# amiketo_2hm.net
KiCad netlist of a schematic drawn in EAGLE
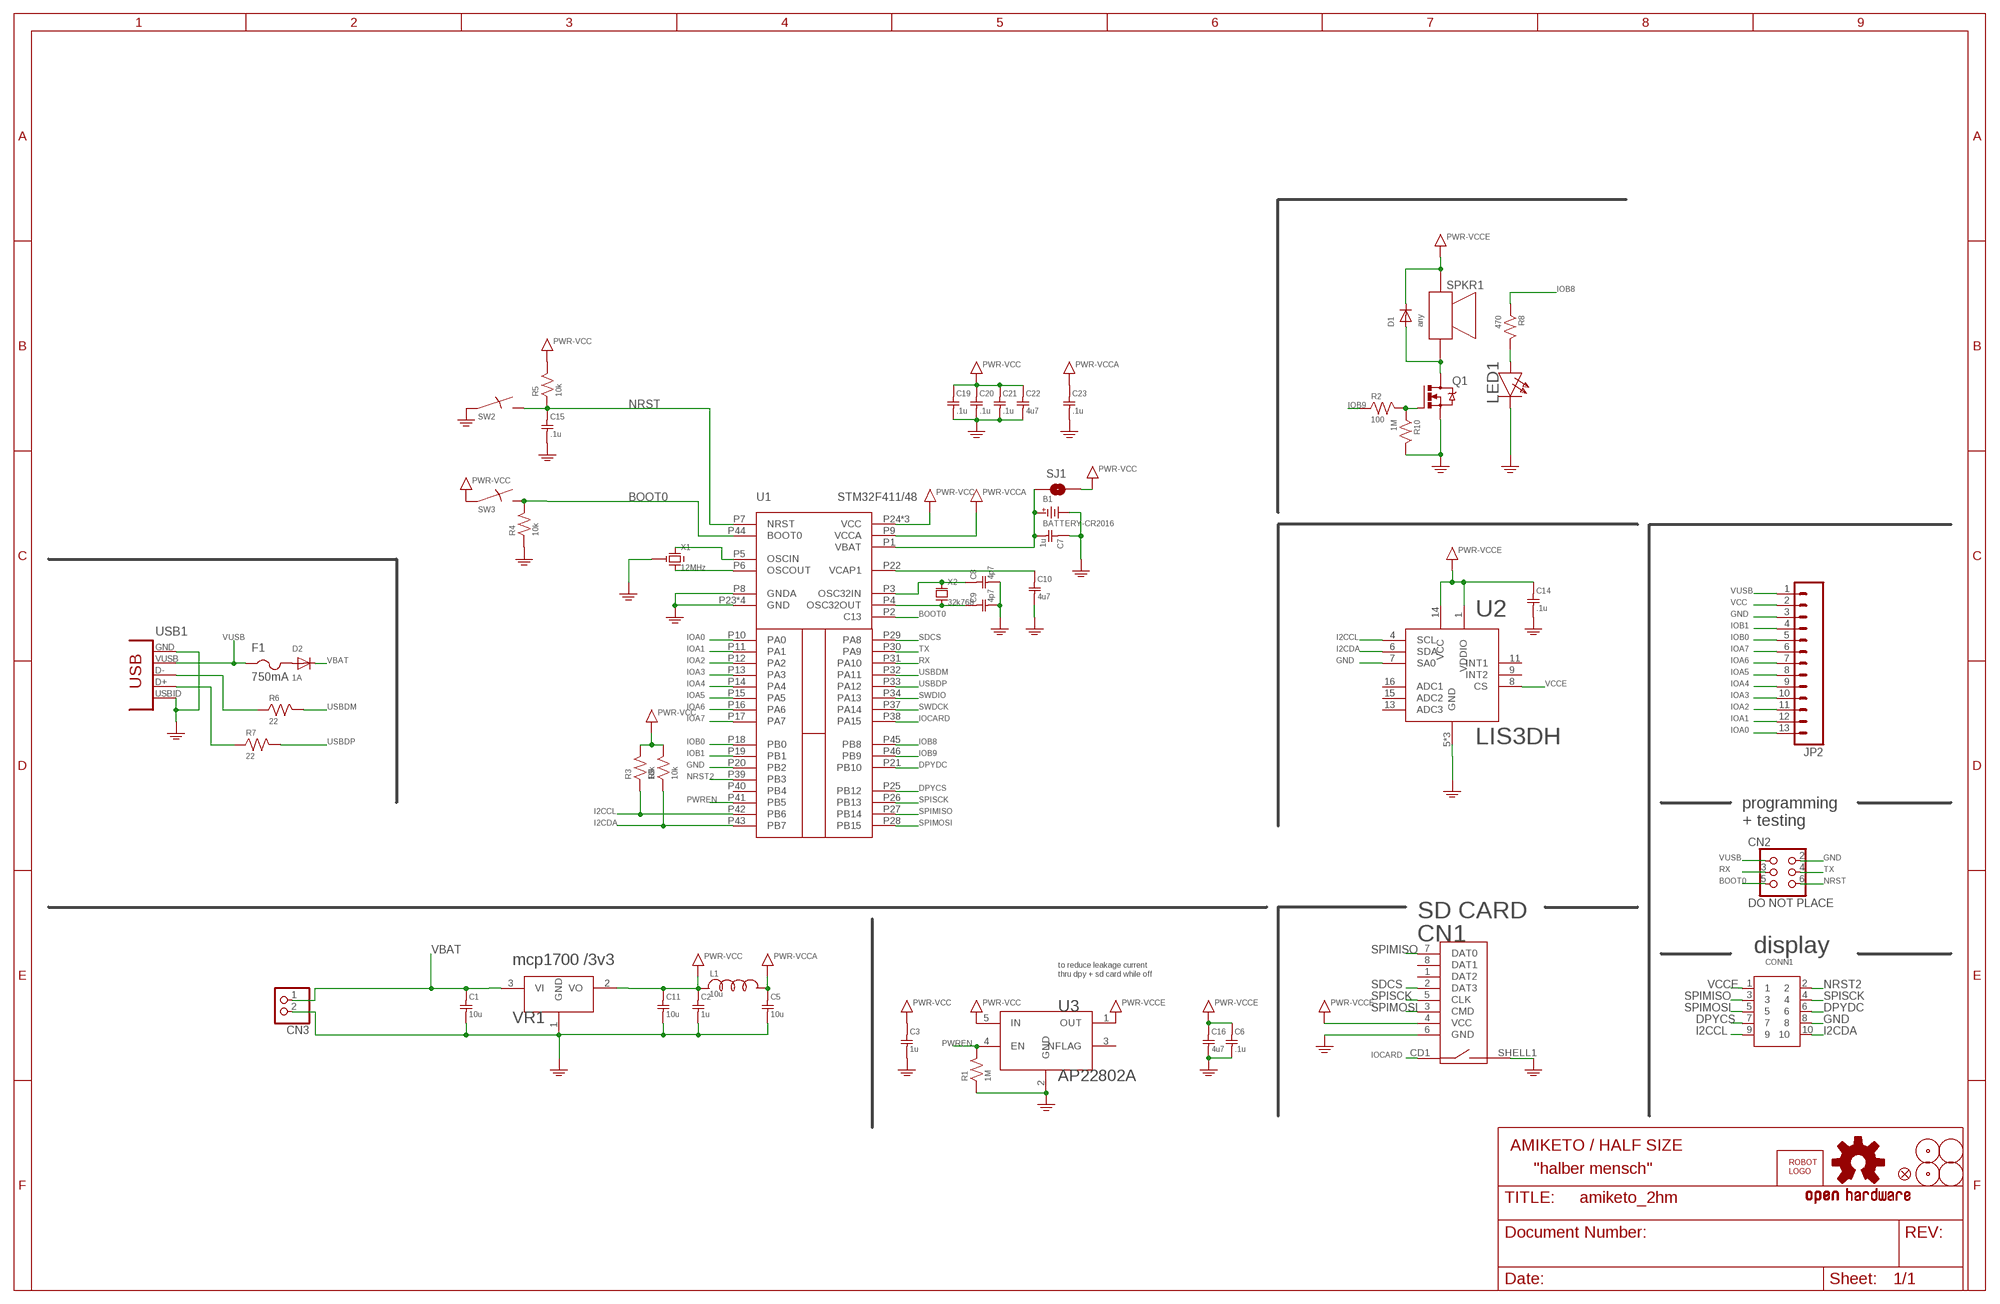
[diagram p0: schematic, sheet 1]

(export (version "E")
  (design (tool "Eeschema 10.0.6"))
  (components
    (comp (ref "B1")
      (value "BATTERY-CR2016")
      (footprint "eagle-import:CR1216")
      (libsource (lib "eagle-import") (part "BATTERY-CR2016"))
    )
    (comp (ref "C1")
      (value "10u")
      (footprint "eagle-import:SMD0603")
      (libsource (lib "eagle-import") (part "C0603"))
    )
    (comp (ref "C2")
      (value "1u")
      (footprint "eagle-import:SMD0603")
      (libsource (lib "eagle-import") (part "C0603"))
    )
    (comp (ref "C3")
      (value "1u")
      (footprint "eagle-import:SMD0603")
      (libsource (lib "eagle-import") (part "C0603"))
    )
    (comp (ref "C5")
      (value "10u")
      (footprint "eagle-import:SMD0603")
      (libsource (lib "eagle-import") (part "C0603"))
    )
    (comp (ref "C6")
      (value ".1u")
      (footprint "eagle-import:SMD0603")
      (libsource (lib "eagle-import") (part "C0603"))
    )
    (comp (ref "C7")
      (value "1u")
      (footprint "eagle-import:SMD0603")
      (libsource (lib "eagle-import") (part "C0603"))
    )
    (comp (ref "C8")
      (value "4p7")
      (footprint "eagle-import:SMD0603")
      (libsource (lib "eagle-import") (part "C0603"))
    )
    (comp (ref "C9")
      (value "4p7")
      (footprint "eagle-import:SMD0603")
      (libsource (lib "eagle-import") (part "C0603"))
    )
    (comp (ref "C10")
      (value "4u7")
      (footprint "eagle-import:SMD0603")
      (libsource (lib "eagle-import") (part "C0603"))
    )
    (comp (ref "C11")
      (value "10u")
      (footprint "eagle-import:SMD0603")
      (libsource (lib "eagle-import") (part "C0603"))
    )
    (comp (ref "C14")
      (value ".1u")
      (footprint "eagle-import:SMD0603")
      (libsource (lib "eagle-import") (part "C0603"))
    )
    (comp (ref "C15")
      (value ".1u")
      (footprint "eagle-import:SMD0603")
      (libsource (lib "eagle-import") (part "C0603"))
    )
    (comp (ref "C16")
      (value "4u7")
      (footprint "eagle-import:SMD0603")
      (libsource (lib "eagle-import") (part "C0603"))
    )
    (comp (ref "C19")
      (value ".1u")
      (footprint "eagle-import:SMD0603")
      (libsource (lib "eagle-import") (part "C0603"))
    )
    (comp (ref "C20")
      (value ".1u")
      (footprint "eagle-import:SMD0603")
      (libsource (lib "eagle-import") (part "C0603"))
    )
    (comp (ref "C21")
      (value ".1u")
      (footprint "eagle-import:SMD0603")
      (libsource (lib "eagle-import") (part "C0603"))
    )
    (comp (ref "C22")
      (value "4u7")
      (footprint "eagle-import:SMD0603")
      (libsource (lib "eagle-import") (part "C0603"))
    )
    (comp (ref "C23")
      (value ".1u")
      (footprint "eagle-import:SMD0603")
      (libsource (lib "eagle-import") (part "C0603"))
    )
    (comp (ref "CN1")
      (value "MICROSD-EJECT")
      (footprint "eagle-import:MICROSD_EJECTOR")
      (libsource (lib "eagle-import") (part "MICROSD-EJECT"))
    )
    (comp (ref "CN2")
      (value "DO NOT PLACE")
      (footprint "eagle-import:HEADER-3X2-POGO")
      (libsource (lib "eagle-import") (part "HEADER-3X2-POGO"))
    )
    (comp (ref "CN3")
      (value "JST_2PIN-SMT-RA")
      (footprint "eagle-import:JST-PH-2-SMT-RA")
      (libsource (lib "eagle-import") (part "JST_2PIN-SMT-RA"))
    )
    (comp (ref "CONN1")
      (value "HEADER-5X2-PTH")
      (footprint "eagle-import:HEADER-5X2-PTH")
      (libsource (lib "eagle-import") (part "HEADER-5X2-PTH"))
    )
    (comp (ref "D1")
      (value "any")
      (footprint "eagle-import:SMD0805D")
      (libsource (lib "eagle-import") (part "DIODE-0805"))
    )
    (comp (ref "D2")
      (value "1A")
      (footprint "eagle-import:SMD0805D")
      (libsource (lib "eagle-import") (part "DIODE-0805"))
    )
    (comp (ref "F1")
      (value "750mA")
      (footprint "eagle-import:SMD1206")
      (libsource (lib "eagle-import") (part "FUSE"))
    )
    (comp (ref "JP2")
      (value "M13")
      (footprint "eagle-import:1X13")
      (libsource (lib "eagle-import") (part "M13"))
    )
    (comp (ref "L1")
      (value "10u")
      (footprint "eagle-import:SMD0603")
      (libsource (lib "eagle-import") (part "LSMD0603"))
    )
    (comp (ref "LED1")
      (value "white")
      (footprint "eagle-import:SMD0603D")
      (libsource (lib "eagle-import") (part "LED"))
    )
    (comp (ref "LOGO1")
      (value "OSHW-LOGOM")
      (footprint "eagle-import:OSHW-LOGO-M")
      (libsource (lib "eagle-import") (part "OSHW-LOGOM"))
    )
    (comp (ref "Q1")
      (value "IRLML6344TRPBF")
      (footprint "eagle-import:SOT-23")
      (libsource (lib "eagle-import") (part "MOSFETSOT-23"))
    )
    (comp (ref "R1")
      (value "1M")
      (footprint "eagle-import:SMD0603")
      (libsource (lib "eagle-import") (part "R0603"))
    )
    (comp (ref "R2")
      (value "100")
      (footprint "eagle-import:SMD0603")
      (libsource (lib "eagle-import") (part "R0603"))
    )
    (comp (ref "R3")
      (value "10k")
      (footprint "eagle-import:SMD0603")
      (libsource (lib "eagle-import") (part "R0603"))
    )
    (comp (ref "R4")
      (value "10k")
      (footprint "eagle-import:SMD0603")
      (libsource (lib "eagle-import") (part "R0603"))
    )
    (comp (ref "R5")
      (value "10k")
      (footprint "eagle-import:SMD0603")
      (libsource (lib "eagle-import") (part "R0603"))
    )
    (comp (ref "R6")
      (value "22")
      (footprint "eagle-import:SMD0603")
      (libsource (lib "eagle-import") (part "R0603"))
    )
    (comp (ref "R7")
      (value "22")
      (footprint "eagle-import:SMD0603")
      (libsource (lib "eagle-import") (part "R0603"))
    )
    (comp (ref "R8")
      (value "470")
      (footprint "eagle-import:SMD0603")
      (libsource (lib "eagle-import") (part "R0603"))
    )
    (comp (ref "R9")
      (value "10k")
      (footprint "eagle-import:SMD0603")
      (libsource (lib "eagle-import") (part "R0603"))
    )
    (comp (ref "R10")
      (value "1M")
      (footprint "eagle-import:SMD0603")
      (libsource (lib "eagle-import") (part "R0603"))
    )
    (comp (ref "SJ1")
      (value "JUMPER-PAD-2-NOYES_SILK")
      (footprint "eagle-import:PAD-JUMPER-2-NO_YES_SILK")
      (libsource (lib "eagle-import") (part "JUMPER-PAD-2-NOYES_SILK"))
    )
    (comp (ref "SPKR1")
      (value "PUI-5040")
      (footprint "eagle-import:PUI-0540")
      (libsource (lib "eagle-import") (part "PUI-5040"))
    )
    (comp (ref "SW2")
      (value "SWITCHKMR211")
      (footprint "eagle-import:KMR211")
      (libsource (lib "eagle-import") (part "SWITCHKMR211"))
    )
    (comp (ref "SW3")
      (value "SWITCHKMR211")
      (footprint "eagle-import:KMR211")
      (libsource (lib "eagle-import") (part "SWITCHKMR211"))
    )
    (comp (ref "U$1")
      (value "FIDUCIAL")
      (footprint "eagle-import:FIDUCIAL")
      (libsource (lib "eagle-import") (part "jaw_FIDUCIAL"))
    )
    (comp (ref "U$2")
      (value "FIDUCIAL")
      (footprint "eagle-import:FIDUCIAL_1MM")
      (libsource (lib "eagle-import") (part "FIDUCIAL"))
    )
    (comp (ref "U$3")
      (value "FIDUCIAL")
      (footprint "eagle-import:FIDUCIAL_1MM")
      (libsource (lib "eagle-import") (part "FIDUCIAL"))
    )
    (comp (ref "U$4")
      (value "ROBOTMAN-LOGO2")
      (footprint "eagle-import:ROBOTMAN-LOGO2")
      (libsource (lib "eagle-import") (part "ROBOTMAN-LOGO2"))
    )
    (comp (ref "U$5")
      (value "FIDUCIAL")
      (footprint "eagle-import:FIDUCIAL")
      (libsource (lib "eagle-import") (part "jaw_FIDUCIAL"))
    )
    (comp (ref "U$6")
      (value "FIDUCIALUFIDUCIAL")
      (footprint "eagle-import:MICRO-FIDUCIAL")
      (libsource (lib "eagle-import") (part "FIDUCIALUFIDUCIAL"))
    )
    (comp (ref "U1")
      (value "STM32F411/48")
      (footprint "eagle-import:UQPFN48")
      (libsource (lib "eagle-import") (part "STM32F411/48"))
    )
    (comp (ref "U2")
      (value "LIS3DH")
      (footprint "eagle-import:LGA16A")
      (libsource (lib "eagle-import") (part "LIS3DH"))
    )
    (comp (ref "U3")
      (value "AP22802A")
      (footprint "eagle-import:SOT-23-5")
      (libsource (lib "eagle-import") (part "NCP380"))
    )
    (comp (ref "USB1")
      (value "CON-USB-F-MICRO-B")
      (footprint "eagle-import:CONN_USB_MICRO-B")
      (libsource (lib "eagle-import") (part "CON-USB-F-MICRO-B"))
    )
    (comp (ref "VR1")
      (value "mcp1700 /3v3")
      (footprint "eagle-import:SOT-23-3")
      (libsource (lib "eagle-import") (part "REGULATOR-SOT23-3"))
    )
    (comp (ref "X1")
      (value "12MHz")
      (footprint "eagle-import:RESONATOR-CSTCE")
      (libsource (lib "eagle-import") (part "RESONATORCTCE"))
    )
    (comp (ref "X2")
      (value "32k768")
      (footprint "eagle-import:XTAL-32X15")
      (libsource (lib "eagle-import") (part "XTAL32X15"))
    )
  )
  (nets
    (net (code "1") (name "/BOOT0") (class "Default")
      (node (ref "CN2") (pin "5") (pinfunction "P$5_5") (pintype "passive"))
      (node (ref "R4") (pin "2") (pinfunction "P$2_2") (pintype "passive"))
      (node (ref "SW3") (pin "2") (pinfunction "P$2_2") (pintype "passive"))
      (node (ref "SW3") (pin "4") (pinfunction "P$2_4") (pintype "passive"))
      (node (ref "U1") (pin "P2") (pinfunction "C13_P2") (pintype "bidirectional"))
      (node (ref "U1") (pin "P44") (pinfunction "BOOT0_P44") (pintype "bidirectional"))
    )
    (net (code "2") (name "/DPYCS") (class "Default")
      (node (ref "CONN1") (pin "7") (pinfunction "7_7") (pintype "passive"))
      (node (ref "U1") (pin "P25") (pinfunction "PB12_P25") (pintype "bidirectional"))
    )
    (net (code "3") (name "/DPYDC") (class "Default")
      (node (ref "CONN1") (pin "6") (pinfunction "6_6") (pintype "passive"))
      (node (ref "U1") (pin "P21") (pinfunction "PB10_P21") (pintype "bidirectional"))
    )
    (net (code "4") (name "/I2CCL") (class "Default")
      (node (ref "CONN1") (pin "9") (pinfunction "9_9") (pintype "passive"))
      (node (ref "R3") (pin "1") (pinfunction "P$1_1") (pintype "passive"))
      (node (ref "U1") (pin "P42") (pinfunction "PB6_P42") (pintype "bidirectional"))
      (node (ref "U2") (pin "4") (pinfunction "SCL_4") (pintype "bidirectional"))
    )
    (net (code "5") (name "/I2CDA") (class "Default")
      (node (ref "CONN1") (pin "10") (pinfunction "10_10") (pintype "passive"))
      (node (ref "R9") (pin "1") (pinfunction "P$1_1") (pintype "passive"))
      (node (ref "U1") (pin "P43") (pinfunction "PB7_P43") (pintype "bidirectional"))
      (node (ref "U2") (pin "6") (pinfunction "SDA_6") (pintype "bidirectional"))
    )
    (net (code "6") (name "/IOA0") (class "Default")
      (node (ref "JP2") (pin "13") (pinfunction "13_13") (pintype "passive"))
      (node (ref "U1") (pin "P10") (pinfunction "PA0_P10") (pintype "bidirectional"))
    )
    (net (code "7") (name "/IOA1") (class "Default")
      (node (ref "JP2") (pin "12") (pinfunction "12_12") (pintype "passive"))
      (node (ref "U1") (pin "P11") (pinfunction "PA1_P11") (pintype "bidirectional"))
    )
    (net (code "8") (name "/IOA2") (class "Default")
      (node (ref "JP2") (pin "11") (pinfunction "11_11") (pintype "passive"))
      (node (ref "U1") (pin "P12") (pinfunction "PA2_P12") (pintype "bidirectional"))
    )
    (net (code "9") (name "/IOA3") (class "Default")
      (node (ref "JP2") (pin "10") (pinfunction "10_10") (pintype "passive"))
      (node (ref "U1") (pin "P13") (pinfunction "PA3_P13") (pintype "bidirectional"))
    )
    (net (code "10") (name "/IOA4") (class "Default")
      (node (ref "JP2") (pin "9") (pinfunction "9_9") (pintype "passive"))
      (node (ref "U1") (pin "P14") (pinfunction "PA4_P14") (pintype "bidirectional"))
    )
    (net (code "11") (name "/IOA5") (class "Default")
      (node (ref "JP2") (pin "8") (pinfunction "8_8") (pintype "passive"))
      (node (ref "U1") (pin "P15") (pinfunction "PA5_P15") (pintype "bidirectional"))
    )
    (net (code "12") (name "/IOA6") (class "Default")
      (node (ref "JP2") (pin "7") (pinfunction "7_7") (pintype "passive"))
      (node (ref "U1") (pin "P16") (pinfunction "PA6_P16") (pintype "bidirectional"))
    )
    (net (code "13") (name "/IOA7") (class "Default")
      (node (ref "JP2") (pin "6") (pinfunction "6_6") (pintype "passive"))
      (node (ref "U1") (pin "P17") (pinfunction "PA7_P17") (pintype "bidirectional"))
    )
    (net (code "14") (name "/IOB0") (class "Default")
      (node (ref "JP2") (pin "5") (pinfunction "5_5") (pintype "passive"))
      (node (ref "U1") (pin "P18") (pinfunction "PB0_P18") (pintype "bidirectional"))
    )
    (net (code "15") (name "/IOB1") (class "Default")
      (node (ref "JP2") (pin "4") (pinfunction "4_4") (pintype "passive"))
      (node (ref "U1") (pin "P19") (pinfunction "PB1_P19") (pintype "bidirectional"))
    )
    (net (code "16") (name "/IOB8") (class "Default")
      (node (ref "R8") (pin "1") (pinfunction "P$1_1") (pintype "passive"))
      (node (ref "U1") (pin "P45") (pinfunction "PB8_P45") (pintype "bidirectional"))
    )
    (net (code "17") (name "/IOB9") (class "Default")
      (node (ref "R2") (pin "1") (pinfunction "P$1_1") (pintype "passive"))
      (node (ref "U1") (pin "P46") (pinfunction "PB9_P46") (pintype "bidirectional"))
    )
    (net (code "18") (name "/IOCARD") (class "Default")
      (node (ref "CN1") (pin "CD1") (pinfunction "SW1_CD1") (pintype "bidirectional"))
      (node (ref "U1") (pin "P38") (pinfunction "PA15_P38") (pintype "bidirectional"))
    )
    (net (code "19") (name "/NRST") (class "Default")
      (node (ref "C15") (pin "1") (pinfunction "P$1_1") (pintype "passive"))
      (node (ref "CN2") (pin "6") (pinfunction "P$6_6") (pintype "passive"))
      (node (ref "R5") (pin "1") (pinfunction "P$1_1") (pintype "passive"))
      (node (ref "SW2") (pin "2") (pinfunction "P$2_2") (pintype "passive"))
      (node (ref "SW2") (pin "4") (pinfunction "P$2_4") (pintype "passive"))
      (node (ref "U1") (pin "P7") (pinfunction "NRST_P7") (pintype "bidirectional"))
    )
    (net (code "20") (name "/NRST2") (class "Default")
      (node (ref "CONN1") (pin "2") (pinfunction "2_2") (pintype "passive"))
      (node (ref "U1") (pin "P39") (pinfunction "PB3_P39") (pintype "bidirectional"))
    )
    (net (code "21") (name "/PWREN") (class "Default")
      (node (ref "R1") (pin "2") (pinfunction "P$2_2") (pintype "passive"))
      (node (ref "U1") (pin "P41") (pinfunction "PB5_P41") (pintype "bidirectional"))
      (node (ref "U3") (pin "4") (pinfunction "EN_4") (pintype "bidirectional"))
    )
    (net (code "22") (name "/RX") (class "Default")
      (node (ref "CN2") (pin "3") (pinfunction "P$3_3") (pintype "passive"))
      (node (ref "U1") (pin "P31") (pinfunction "PA10_P31") (pintype "bidirectional"))
    )
    (net (code "23") (name "/SDCS") (class "Default")
      (node (ref "CN1") (pin "2") (pinfunction "DAT3_2") (pintype "bidirectional"))
      (node (ref "U1") (pin "P29") (pinfunction "PA8_P29") (pintype "bidirectional"))
    )
    (net (code "24") (name "/SPIMISO") (class "Default")
      (node (ref "CN1") (pin "7") (pinfunction "DAT0_7") (pintype "bidirectional"))
      (node (ref "CONN1") (pin "3") (pinfunction "3_3") (pintype "passive"))
      (node (ref "U1") (pin "P27") (pinfunction "PB14_P27") (pintype "bidirectional"))
    )
    (net (code "25") (name "/SPIMOSI") (class "Default")
      (node (ref "CN1") (pin "3") (pinfunction "CMD_3") (pintype "bidirectional"))
      (node (ref "CONN1") (pin "5") (pinfunction "5_5") (pintype "passive"))
      (node (ref "U1") (pin "P28") (pinfunction "PB15_P28") (pintype "bidirectional"))
    )
    (net (code "26") (name "/SPISCK") (class "Default")
      (node (ref "CN1") (pin "5") (pinfunction "CLK_5") (pintype "bidirectional"))
      (node (ref "CONN1") (pin "4") (pinfunction "4_4") (pintype "passive"))
      (node (ref "U1") (pin "P26") (pinfunction "PB13_P26") (pintype "bidirectional"))
    )
    (net (code "27") (name "/SWDCK") (class "Default")
      (node (ref "U1") (pin "P37") (pinfunction "PA14_P37") (pintype "bidirectional"))
    )
    (net (code "28") (name "/SWDIO") (class "Default")
      (node (ref "U1") (pin "P34") (pinfunction "PA13_P34") (pintype "bidirectional"))
    )
    (net (code "29") (name "/TX") (class "Default")
      (node (ref "CN2") (pin "4") (pinfunction "P$4_4") (pintype "passive"))
      (node (ref "U1") (pin "P30") (pinfunction "PA9_P30") (pintype "bidirectional"))
    )
    (net (code "30") (name "/USBDM") (class "Default")
      (node (ref "R6") (pin "2") (pinfunction "P$2_2") (pintype "passive"))
      (node (ref "U1") (pin "P32") (pinfunction "PA11_P32") (pintype "bidirectional"))
    )
    (net (code "31") (name "/USBDP") (class "Default")
      (node (ref "R7") (pin "2") (pinfunction "P$2_2") (pintype "passive"))
      (node (ref "U1") (pin "P33") (pinfunction "PA12_P33") (pintype "bidirectional"))
    )
    (net (code "32") (name "/VBAT") (class "Default")
      (node (ref "C1") (pin "1") (pinfunction "P$1_1") (pintype "passive"))
      (node (ref "CN3") (pin "1") (pinfunction "2_1") (pintype "passive"))
      (node (ref "D2") (pin "C") (pinfunction "C_C") (pintype "passive"))
      (node (ref "VR1") (pin "3") (pinfunction "VI_3") (pintype "bidirectional"))
    )
    (net (code "33") (name "/VUSB") (class "Default")
      (node (ref "CN2") (pin "1") (pinfunction "P$1_1") (pintype "passive"))
      (node (ref "F1") (pin "1") (pinfunction "1_1") (pintype "passive"))
      (node (ref "JP2") (pin "1") (pinfunction "1_1") (pintype "passive"))
      (node (ref "USB1") (pin "P1") (pinfunction "VUSB_P1") (pintype "bidirectional"))
    )
    (net (code "34") (name "Net-(C7-P$2)") (class "Default")
      (node (ref "B1") (pin "PLUS1") (pinfunction "P_PLUS1") (pintype "bidirectional"))
      (node (ref "B1") (pin "PLUS2") (pinfunction "P_PLUS2") (pintype "bidirectional"))
      (node (ref "C7") (pin "2") (pinfunction "P$2_2") (pintype "passive"))
      (node (ref "SJ1") (pin "1") (pinfunction "1_1") (pintype "passive"))
      (node (ref "U1") (pin "P1") (pinfunction "VBAT_P1") (pintype "bidirectional"))
    )
    (net (code "35") (name "Net-(C8-P$1)") (class "Default")
      (node (ref "C8") (pin "1") (pinfunction "P$1_1") (pintype "passive"))
      (node (ref "U1") (pin "P3") (pinfunction "OSC32IN_P3") (pintype "bidirectional"))
      (node (ref "X2") (pin "P$1") (pinfunction "P$1_P$1") (pintype "passive"))
    )
    (net (code "36") (name "Net-(C9-P$1)") (class "Default")
      (node (ref "C9") (pin "1") (pinfunction "P$1_1") (pintype "passive"))
      (node (ref "U1") (pin "P4") (pinfunction "OSC32OUT_P4") (pintype "bidirectional"))
      (node (ref "X2") (pin "P$2") (pinfunction "P$2_P$2") (pintype "passive"))
    )
    (net (code "37") (name "Net-(C10-P$1)") (class "Default")
      (node (ref "C10") (pin "1") (pinfunction "P$1_1") (pintype "passive"))
      (node (ref "U1") (pin "P22") (pinfunction "VCAP1_P22") (pintype "bidirectional"))
    )
    (net (code "38") (name "Net-(D2-PadA)") (class "Default")
      (node (ref "D2") (pin "A") (pinfunction "A_A") (pintype "passive"))
      (node (ref "F1") (pin "2") (pinfunction "2_2") (pintype "passive"))
    )
    (net (code "39") (name "Net-(Q1-D)") (class "Default")
      (node (ref "D1") (pin "A") (pinfunction "A_A") (pintype "passive"))
      (node (ref "Q1") (pin "3") (pinfunction "D_3") (pintype "passive"))
      (node (ref "SPKR1") (pin "P2") (pinfunction "P2_P2") (pintype "input"))
    )
    (net (code "40") (name "Net-(Q1-G)") (class "Default")
      (node (ref "Q1") (pin "1") (pinfunction "G_1") (pintype "passive"))
      (node (ref "R10") (pin "1") (pinfunction "P$1_1") (pintype "passive"))
      (node (ref "R2") (pin "2") (pinfunction "P$2_2") (pintype "passive"))
    )
    (net (code "41") (name "Net-(R6-P$1)") (class "Default")
      (node (ref "R6") (pin "1") (pinfunction "P$1_1") (pintype "passive"))
      (node (ref "USB1") (pin "P2") (pinfunction "D-_P2") (pintype "bidirectional"))
    )
    (net (code "42") (name "Net-(R7-P$1)") (class "Default")
      (node (ref "R7") (pin "1") (pinfunction "P$1_1") (pintype "passive"))
      (node (ref "USB1") (pin "P3") (pinfunction "D+_P3") (pintype "bidirectional"))
    )
    (net (code "43") (name "Net-(R8-P$2)") (class "Default")
      (node (ref "LED1") (pin "A") (pinfunction "A_A") (pintype "passive"))
      (node (ref "R8") (pin "2") (pinfunction "P$2_2") (pintype "passive"))
    )
    (net (code "44") (name "Net-(U1-OSCIN)") (class "Default")
      (node (ref "U1") (pin "P5") (pinfunction "OSCIN_P5") (pintype "bidirectional"))
      (node (ref "X1") (pin "1") (pinfunction "X1_1") (pintype "passive"))
    )
    (net (code "45") (name "Net-(U1-OSCOUT)") (class "Default")
      (node (ref "U1") (pin "P6") (pinfunction "OSCOUT_P6") (pintype "bidirectional"))
      (node (ref "X1") (pin "3") (pinfunction "X2_3") (pintype "passive"))
    )
    (net (code "46") (name "PWR-GND") (class "Default")
      (node (ref "B1") (pin "MINUS") (pinfunction "M_MINUS") (pintype "bidirectional"))
      (node (ref "C1") (pin "2") (pinfunction "P$2_2") (pintype "passive"))
      (node (ref "C10") (pin "2") (pinfunction "P$2_2") (pintype "passive"))
      (node (ref "C11") (pin "2") (pinfunction "P$2_2") (pintype "passive"))
      (node (ref "C14") (pin "2") (pinfunction "P$2_2") (pintype "passive"))
      (node (ref "C15") (pin "2") (pinfunction "P$2_2") (pintype "passive"))
      (node (ref "C16") (pin "2") (pinfunction "P$2_2") (pintype "passive"))
      (node (ref "C19") (pin "2") (pinfunction "P$2_2") (pintype "passive"))
      (node (ref "C2") (pin "2") (pinfunction "P$2_2") (pintype "passive"))
      (node (ref "C20") (pin "2") (pinfunction "P$2_2") (pintype "passive"))
      (node (ref "C21") (pin "2") (pinfunction "P$2_2") (pintype "passive"))
      (node (ref "C22") (pin "2") (pinfunction "P$2_2") (pintype "passive"))
      (node (ref "C23") (pin "2") (pinfunction "P$2_2") (pintype "passive"))
      (node (ref "C3") (pin "2") (pinfunction "P$2_2") (pintype "passive"))
      (node (ref "C5") (pin "2") (pinfunction "P$2_2") (pintype "passive"))
      (node (ref "C6") (pin "2") (pinfunction "P$2_2") (pintype "passive"))
      (node (ref "C7") (pin "1") (pinfunction "P$1_1") (pintype "passive"))
      (node (ref "C8") (pin "2") (pinfunction "P$2_2") (pintype "passive"))
      (node (ref "C9") (pin "2") (pinfunction "P$2_2") (pintype "passive"))
      (node (ref "CN1") (pin "6") (pinfunction "GND_6") (pintype "bidirectional"))
      (node (ref "CN1") (pin "SHELL1") (pinfunction "SW2_SHELL1") (pintype "bidirectional"))
      (node (ref "CN2") (pin "2") (pinfunction "P$2_2") (pintype "passive"))
      (node (ref "CN3") (pin "2") (pinfunction "1_2") (pintype "passive"))
      (node (ref "CONN1") (pin "8") (pinfunction "8_8") (pintype "passive"))
      (node (ref "JP2") (pin "3") (pinfunction "3_3") (pintype "passive"))
      (node (ref "LED1") (pin "C") (pinfunction "C_C") (pintype "passive"))
      (node (ref "Q1") (pin "2") (pinfunction "S_2") (pintype "passive"))
      (node (ref "R1") (pin "1") (pinfunction "P$1_1") (pintype "passive"))
      (node (ref "R10") (pin "2") (pinfunction "P$2_2") (pintype "passive"))
      (node (ref "R4") (pin "1") (pinfunction "P$1_1") (pintype "passive"))
      (node (ref "SW2") (pin "1") (pinfunction "P$1_1") (pintype "passive"))
      (node (ref "SW2") (pin "3") (pinfunction "P$1_3") (pintype "passive"))
      (node (ref "U1") (pin "P20") (pinfunction "PB2_P20") (pintype "bidirectional"))
      (node (ref "U1") (pin "P23") (pinfunction "GND_P23") (pintype "bidirectional"))
      (node (ref "U1") (pin "P35") (pinfunction "GND_P35") (pintype "bidirectional"))
      (node (ref "U1") (pin "P47") (pinfunction "GND_P47") (pintype "bidirectional"))
      (node (ref "U1") (pin "P8") (pinfunction "GNDA_P8") (pintype "bidirectional"))
      (node (ref "U1") (pin "PAD") (pinfunction "GND_PAD") (pintype "bidirectional"))
      (node (ref "U2") (pin "10") (pinfunction "GND_10") (pintype "power_in"))
      (node (ref "U2") (pin "12") (pinfunction "GND_12") (pintype "power_in"))
      (node (ref "U2") (pin "5") (pinfunction "GND_5") (pintype "power_in"))
      (node (ref "U2") (pin "7") (pinfunction "SA0_7") (pintype "bidirectional"))
      (node (ref "U3") (pin "2") (pinfunction "GND_2") (pintype "bidirectional"))
      (node (ref "USB1") (pin "P4") (pinfunction "USBID_P4") (pintype "bidirectional"))
      (node (ref "USB1") (pin "P5") (pinfunction "GND_P5") (pintype "bidirectional"))
      (node (ref "VR1") (pin "1") (pinfunction "GND_1") (pintype "bidirectional"))
      (node (ref "X1") (pin "2") (pinfunction "G_2") (pintype "input"))
    )
    (net (code "47") (name "PWR-VCC") (class "Default")
      (node (ref "C11") (pin "1") (pinfunction "P$1_1") (pintype "passive"))
      (node (ref "C19") (pin "1") (pinfunction "P$1_1") (pintype "passive"))
      (node (ref "C2") (pin "1") (pinfunction "P$1_1") (pintype "passive"))
      (node (ref "C20") (pin "1") (pinfunction "P$1_1") (pintype "passive"))
      (node (ref "C21") (pin "1") (pinfunction "P$1_1") (pintype "passive"))
      (node (ref "C22") (pin "1") (pinfunction "P$1_1") (pintype "passive"))
      (node (ref "C3") (pin "1") (pinfunction "P$1_1") (pintype "passive"))
      (node (ref "JP2") (pin "2") (pinfunction "2_2") (pintype "passive"))
      (node (ref "L1") (pin "1") (pinfunction "P$1_1") (pintype "passive"))
      (node (ref "R3") (pin "2") (pinfunction "P$2_2") (pintype "passive"))
      (node (ref "R5") (pin "2") (pinfunction "P$2_2") (pintype "passive"))
      (node (ref "R9") (pin "2") (pinfunction "P$2_2") (pintype "passive"))
      (node (ref "SJ1") (pin "2") (pinfunction "2_2") (pintype "passive"))
      (node (ref "SW3") (pin "1") (pinfunction "P$1_1") (pintype "passive"))
      (node (ref "SW3") (pin "3") (pinfunction "P$1_3") (pintype "passive"))
      (node (ref "U1") (pin "P24") (pinfunction "VCC_P24") (pintype "bidirectional"))
      (node (ref "U1") (pin "P36") (pinfunction "VCC_P36") (pintype "bidirectional"))
      (node (ref "U1") (pin "P48") (pinfunction "VCC_P48") (pintype "bidirectional"))
      (node (ref "U3") (pin "5") (pinfunction "IN_5") (pintype "bidirectional"))
      (node (ref "VR1") (pin "2") (pinfunction "VO_2") (pintype "bidirectional"))
    )
    (net (code "48") (name "PWR-VCCA") (class "Default")
      (node (ref "C23") (pin "1") (pinfunction "P$1_1") (pintype "passive"))
      (node (ref "C5") (pin "1") (pinfunction "P$1_1") (pintype "passive"))
      (node (ref "L1") (pin "2") (pinfunction "P$2_2") (pintype "passive"))
      (node (ref "U1") (pin "P9") (pinfunction "VCCA_P9") (pintype "bidirectional"))
    )
    (net (code "49") (name "PWR-VCCE") (class "Default")
      (node (ref "C14") (pin "1") (pinfunction "P$1_1") (pintype "passive"))
      (node (ref "C16") (pin "1") (pinfunction "P$1_1") (pintype "passive"))
      (node (ref "C6") (pin "1") (pinfunction "P$1_1") (pintype "passive"))
      (node (ref "CN1") (pin "4") (pinfunction "VCC_4") (pintype "bidirectional"))
      (node (ref "CONN1") (pin "1") (pinfunction "1_1") (pintype "passive"))
      (node (ref "D1") (pin "C") (pinfunction "C_C") (pintype "passive"))
      (node (ref "SPKR1") (pin "P1") (pinfunction "P1_P1") (pintype "input"))
      (node (ref "U2") (pin "1") (pinfunction "VDDIO_1") (pintype "bidirectional"))
      (node (ref "U2") (pin "14") (pinfunction "VCC_14") (pintype "power_in"))
      (node (ref "U2") (pin "8") (pinfunction "CS_8") (pintype "bidirectional"))
      (node (ref "U3") (pin "1") (pinfunction "OUT_1") (pintype "bidirectional"))
    )
    (net (code "50") (name "unconnected-(CN1-DAT1-Pad8)") (class "Default")
      (node (ref "CN1") (pin "8") (pinfunction "DAT1_8") (pintype "bidirectional"))
    )
    (net (code "51") (name "unconnected-(CN1-DAT2-Pad1)") (class "Default")
      (node (ref "CN1") (pin "1") (pinfunction "DAT2_1") (pintype "bidirectional"))
    )
    (net (code "52") (name "unconnected-(U1-PB4-PadP40)") (class "Default")
      (node (ref "U1") (pin "P40") (pinfunction "PB4_P40") (pintype "bidirectional"))
    )
    (net (code "53") (name "unconnected-(U2-ADC1-Pad16)") (class "Default")
      (node (ref "U2") (pin "16") (pinfunction "ADC1_16") (pintype "bidirectional"))
    )
    (net (code "54") (name "unconnected-(U2-ADC2-Pad15)") (class "Default")
      (node (ref "U2") (pin "15") (pinfunction "ADC2_15") (pintype "bidirectional"))
    )
    (net (code "55") (name "unconnected-(U2-ADC3-Pad13)") (class "Default")
      (node (ref "U2") (pin "13") (pinfunction "ADC3_13") (pintype "bidirectional"))
    )
    (net (code "56") (name "unconnected-(U2-INT1-Pad11)") (class "Default")
      (node (ref "U2") (pin "11") (pinfunction "INT1_11") (pintype "bidirectional"))
    )
    (net (code "57") (name "unconnected-(U2-INT2-Pad9)") (class "Default")
      (node (ref "U2") (pin "9") (pinfunction "INT2_9") (pintype "bidirectional"))
    )
    (net (code "58") (name "unconnected-(U3-NFLAG-Pad3)") (class "Default")
      (node (ref "U3") (pin "3") (pinfunction "NFLAG_3") (pintype "bidirectional"))
    )
  )
)
